# ABS_ENC_IF.net
KiCad netlist of a schematic drawn in Altium Designer
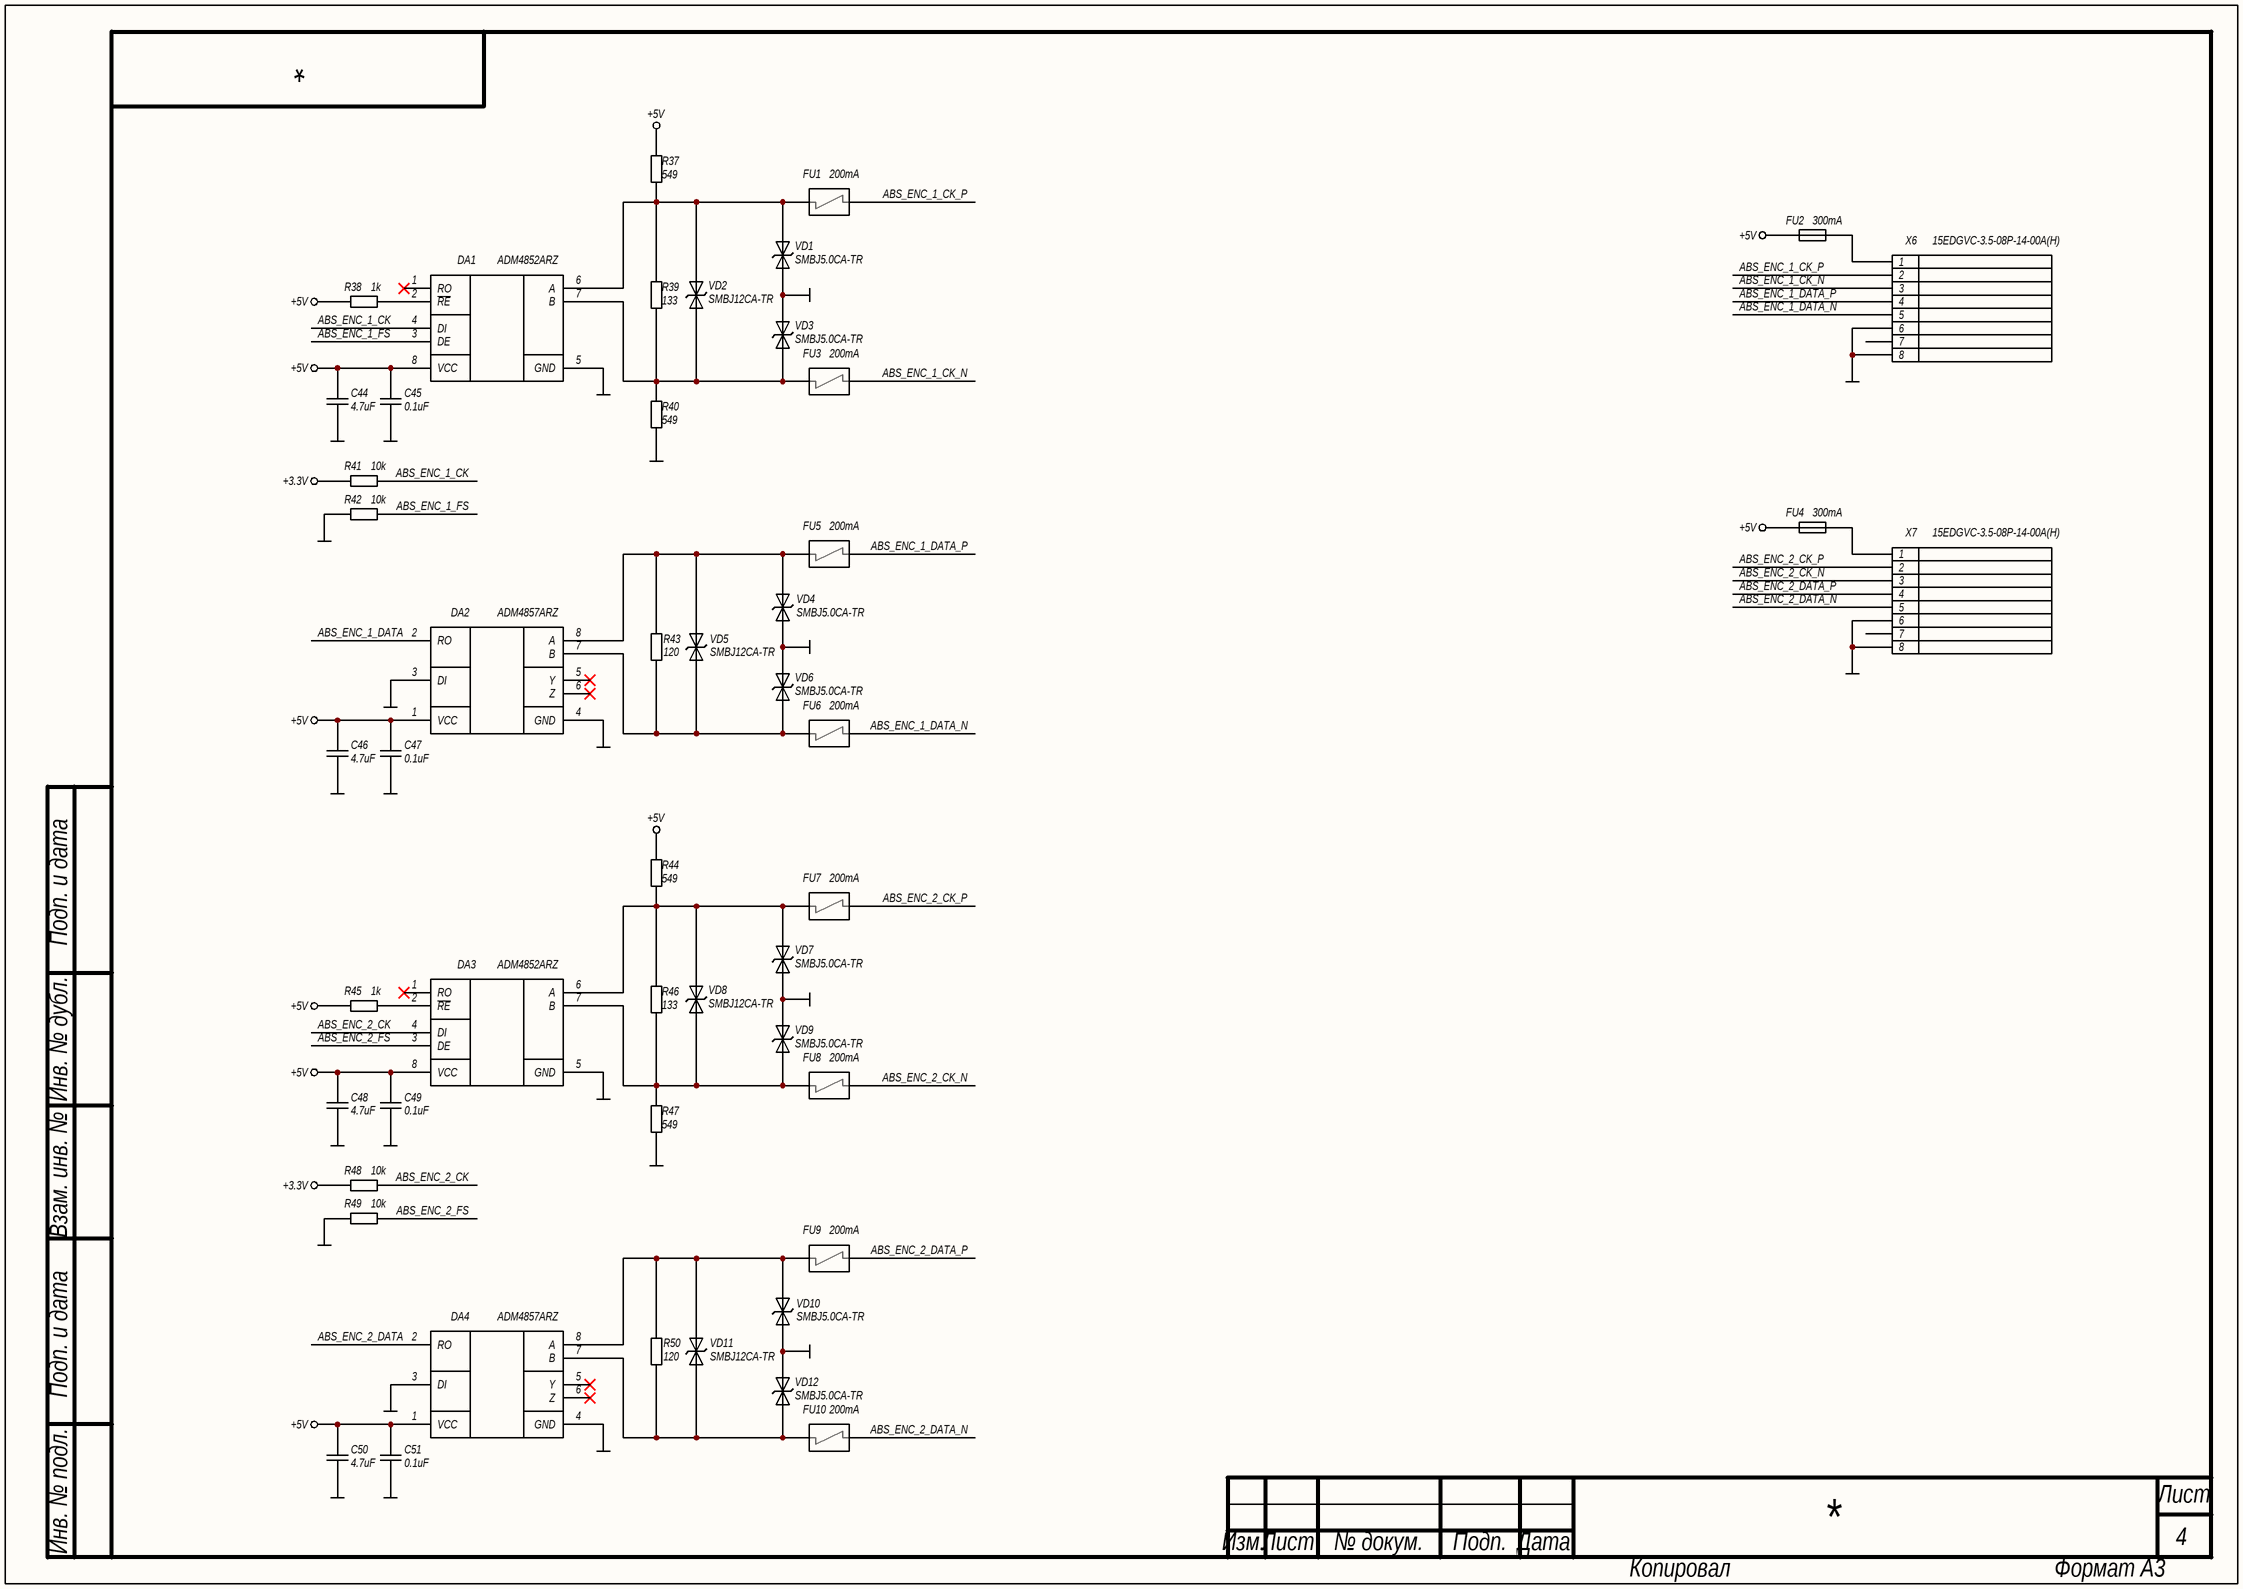
[diagram p0: ABS_ENC_IF.SchDoc]

(export (version "E")
  (design (tool "Eeschema 10.0.6"))
  (components
    (comp (ref "C44")
      (value "4.7uF")
      (footprint "C0603N")
      (description "Конденсатор")
      (libsource (lib "Components Library") (part "CAP_FIXED"))
    )
    (comp (ref "C45")
      (value "0.1uF")
      (footprint "C0603N")
      (description "Конденсатор")
      (libsource (lib "Components Library") (part "CAP_FIXED"))
    )
    (comp (ref "C46")
      (value "4.7uF")
      (footprint "C0603N")
      (description "Конденсатор")
      (libsource (lib "Components Library") (part "CAP_FIXED"))
    )
    (comp (ref "C47")
      (value "0.1uF")
      (footprint "C0603N")
      (description "Конденсатор")
      (libsource (lib "Components Library") (part "CAP_FIXED"))
    )
    (comp (ref "C48")
      (value "4.7uF")
      (footprint "C0603N")
      (description "Конденсатор")
      (libsource (lib "Components Library") (part "CAP_FIXED"))
    )
    (comp (ref "C49")
      (value "0.1uF")
      (footprint "C0603N")
      (description "Конденсатор")
      (libsource (lib "Components Library") (part "CAP_FIXED"))
    )
    (comp (ref "C50")
      (value "4.7uF")
      (footprint "C0603N")
      (description "Конденсатор")
      (libsource (lib "Components Library") (part "CAP_FIXED"))
    )
    (comp (ref "C51")
      (value "0.1uF")
      (footprint "C0603N")
      (description "Конденсатор")
      (libsource (lib "Components Library") (part "CAP_FIXED"))
    )
    (comp (ref "DA1")
      (value "ADM4852ARZ")
      (footprint "SOIC8")
      (description "Микросхема интерфейса RS485")
      (libsource (lib "Components Library") (part "ADM4852A"))
    )
    (comp (ref "DA2")
      (value "ADM4857ARZ")
      (footprint "SOIC8")
      (description "Микросхема интерфейса RS485")
      (libsource (lib "Components Library") (part "ADM4857A"))
    )
    (comp (ref "DA3")
      (value "ADM4852ARZ")
      (footprint "SOIC8")
      (description "Микросхема интерфейса RS485")
      (libsource (lib "Components Library") (part "ADM4852A"))
    )
    (comp (ref "DA4")
      (value "ADM4857ARZ")
      (footprint "SOIC8")
      (description "Микросхема интерфейса RS485")
      (libsource (lib "Components Library") (part "ADM4857A"))
    )
    (comp (ref "FU1")
      (value "200mA")
      (footprint "TBU-CA")
      (description "Полупроводниковый предохранитель")
      (libsource (lib "Components Library") (part "FUSE_TBU"))
    )
    (comp (ref "FU2")
      (value "300mA")
      (footprint "MF-MSMF")
      (description "Плавкий предохранитель")
      (libsource (lib "Components Library") (part "FUSE"))
    )
    (comp (ref "FU3")
      (value "200mA")
      (footprint "TBU-CA")
      (description "Полупроводниковый предохранитель")
      (libsource (lib "Components Library") (part "FUSE_TBU"))
    )
    (comp (ref "FU4")
      (value "300mA")
      (footprint "MF-MSMF")
      (description "Плавкий предохранитель")
      (libsource (lib "Components Library") (part "FUSE"))
    )
    (comp (ref "FU5")
      (value "200mA")
      (footprint "TBU-CA")
      (description "Полупроводниковый предохранитель")
      (libsource (lib "Components Library") (part "FUSE_TBU"))
    )
    (comp (ref "FU6")
      (value "200mA")
      (footprint "TBU-CA")
      (description "Полупроводниковый предохранитель")
      (libsource (lib "Components Library") (part "FUSE_TBU"))
    )
    (comp (ref "FU7")
      (value "200mA")
      (footprint "TBU-CA")
      (description "Полупроводниковый предохранитель")
      (libsource (lib "Components Library") (part "FUSE_TBU"))
    )
    (comp (ref "FU8")
      (value "200mA")
      (footprint "TBU-CA")
      (description "Полупроводниковый предохранитель")
      (libsource (lib "Components Library") (part "FUSE_TBU"))
    )
    (comp (ref "FU9")
      (value "200mA")
      (footprint "TBU-CA")
      (description "Полупроводниковый предохранитель")
      (libsource (lib "Components Library") (part "FUSE_TBU"))
    )
    (comp (ref "FU10")
      (value "200mA")
      (footprint "TBU-CA")
      (description "Полупроводниковый предохранитель")
      (libsource (lib "Components Library") (part "FUSE_TBU"))
    )
    (comp (ref "R37")
      (value "549")
      (footprint "R0805N")
      (description "Резистор")
      (libsource (lib "") (part "RES_FIXED_2"))
    )
    (comp (ref "R38")
      (value "1k")
      (footprint "R0603N")
      (description "Резистор")
      (libsource (lib "Components Library") (part "RES_FIXED"))
    )
    (comp (ref "R39")
      (value "133")
      (footprint "R0805N")
      (description "Резистор")
      (libsource (lib "") (part "RES_FIXED_2"))
    )
    (comp (ref "R40")
      (value "549")
      (footprint "R0805N")
      (description "Резистор")
      (libsource (lib "") (part "RES_FIXED_2"))
    )
    (comp (ref "R41")
      (value "10k")
      (footprint "R0603N")
      (description "Резистор")
      (libsource (lib "Components Library") (part "RES_FIXED"))
    )
    (comp (ref "R42")
      (value "10k")
      (footprint "R0603N")
      (description "Резистор")
      (libsource (lib "Components Library") (part "RES_FIXED"))
    )
    (comp (ref "R43")
      (value "120")
      (footprint "R0805N")
      (description "Резистор")
      (libsource (lib "") (part "RES_FIXED_1"))
    )
    (comp (ref "R44")
      (value "549")
      (footprint "R0805N")
      (description "Резистор")
      (libsource (lib "") (part "RES_FIXED_2"))
    )
    (comp (ref "R45")
      (value "1k")
      (footprint "R0603N")
      (description "Резистор")
      (libsource (lib "Components Library") (part "RES_FIXED"))
    )
    (comp (ref "R46")
      (value "133")
      (footprint "R0805N")
      (description "Резистор")
      (libsource (lib "") (part "RES_FIXED_2"))
    )
    (comp (ref "R47")
      (value "549")
      (footprint "R0805N")
      (description "Резистор")
      (libsource (lib "") (part "RES_FIXED_2"))
    )
    (comp (ref "R48")
      (value "10k")
      (footprint "R0603N")
      (description "Резистор")
      (libsource (lib "Components Library") (part "RES_FIXED"))
    )
    (comp (ref "R49")
      (value "10k")
      (footprint "R0603N")
      (description "Резистор")
      (libsource (lib "Components Library") (part "RES_FIXED"))
    )
    (comp (ref "R50")
      (value "120")
      (footprint "R0805N")
      (description "Резистор")
      (libsource (lib "") (part "RES_FIXED_1"))
    )
    (comp (ref "VD1")
      (value "SMBJ5.0CA-TR")
      (footprint "SMB")
      (description "TVS диод двунаправленный")
      (libsource (lib "Components Library") (part "TVS_BIDIR"))
    )
    (comp (ref "VD2")
      (value "SMBJ12CA-TR")
      (footprint "SMB")
      (description "TVS диод двунаправленный")
      (libsource (lib "Components Library") (part "TVS_BIDIR"))
    )
    (comp (ref "VD3")
      (value "SMBJ5.0CA-TR")
      (footprint "SMB")
      (description "TVS диод двунаправленный")
      (libsource (lib "Components Library") (part "TVS_BIDIR"))
    )
    (comp (ref "VD4")
      (value "SMBJ5.0CA-TR")
      (footprint "SMB")
      (description "TVS диод двунаправленный")
      (libsource (lib "Components Library") (part "TVS_BIDIR"))
    )
    (comp (ref "VD5")
      (value "SMBJ12CA-TR")
      (footprint "SMB")
      (description "TVS диод двунаправленный")
      (libsource (lib "Components Library") (part "TVS_BIDIR"))
    )
    (comp (ref "VD6")
      (value "SMBJ5.0CA-TR")
      (footprint "SMB")
      (description "TVS диод двунаправленный")
      (libsource (lib "Components Library") (part "TVS_BIDIR"))
    )
    (comp (ref "VD7")
      (value "SMBJ5.0CA-TR")
      (footprint "SMB")
      (description "TVS диод двунаправленный")
      (libsource (lib "Components Library") (part "TVS_BIDIR"))
    )
    (comp (ref "VD8")
      (value "SMBJ12CA-TR")
      (footprint "SMB")
      (description "TVS диод двунаправленный")
      (libsource (lib "Components Library") (part "TVS_BIDIR"))
    )
    (comp (ref "VD9")
      (value "SMBJ5.0CA-TR")
      (footprint "SMB")
      (description "TVS диод двунаправленный")
      (libsource (lib "Components Library") (part "TVS_BIDIR"))
    )
    (comp (ref "VD10")
      (value "SMBJ5.0CA-TR")
      (footprint "SMB")
      (description "TVS диод двунаправленный")
      (libsource (lib "Components Library") (part "TVS_BIDIR"))
    )
    (comp (ref "VD11")
      (value "SMBJ12CA-TR")
      (footprint "SMB")
      (description "TVS диод двунаправленный")
      (libsource (lib "Components Library") (part "TVS_BIDIR"))
    )
    (comp (ref "VD12")
      (value "SMBJ5.0CA-TR")
      (footprint "SMB")
      (description "TVS диод двунаправленный")
      (libsource (lib "Components Library") (part "TVS_BIDIR"))
    )
    (comp (ref "X6")
      (value "15EDGVC-3.5-08P-14-00A(H)")
      (footprint "15EDGVC-3.5-08P-14-00A(H)")
      (description "Разъем, 8 контактов")
      (libsource (lib "Components Library") (part "Connector 8"))
    )
    (comp (ref "X7")
      (value "15EDGVC-3.5-08P-14-00A(H)")
      (footprint "15EDGVC-3.5-08P-14-00A(H)")
      (description "Разъем, 8 контактов")
      (libsource (lib "Components Library") (part "Connector 8"))
    )
  )
  (nets
    (net (code "1") (name "+3.3V") (class "Default")
      (node (ref "R41") (pin "2") (pinfunction "2_2") (pintype "passive"))
      (node (ref "R48") (pin "2") (pinfunction "2_2") (pintype "passive"))
    )
    (net (code "2") (name "+5V") (class "Default")
      (node (ref "C44") (pin "2") (pinfunction "2_2") (pintype "passive"))
      (node (ref "C45") (pin "2") (pinfunction "2_2") (pintype "passive"))
      (node (ref "C46") (pin "2") (pinfunction "2_2") (pintype "passive"))
      (node (ref "C47") (pin "2") (pinfunction "2_2") (pintype "passive"))
      (node (ref "C48") (pin "2") (pinfunction "2_2") (pintype "passive"))
      (node (ref "C49") (pin "2") (pinfunction "2_2") (pintype "passive"))
      (node (ref "C50") (pin "2") (pinfunction "2_2") (pintype "passive"))
      (node (ref "C51") (pin "2") (pinfunction "2_2") (pintype "passive"))
      (node (ref "DA1") (pin "8") (pinfunction "VCC_8") (pintype "power_in"))
      (node (ref "DA2") (pin "1") (pinfunction "VCC_1") (pintype "power_in"))
      (node (ref "DA3") (pin "8") (pinfunction "VCC_8") (pintype "power_in"))
      (node (ref "DA4") (pin "1") (pinfunction "VCC_1") (pintype "power_in"))
      (node (ref "FU2") (pin "1") (pinfunction "1_1") (pintype "passive"))
      (node (ref "FU4") (pin "1") (pinfunction "1_1") (pintype "passive"))
      (node (ref "R37") (pin "2") (pinfunction "2_2") (pintype "passive"))
      (node (ref "R38") (pin "2") (pinfunction "2_2") (pintype "passive"))
      (node (ref "R44") (pin "2") (pinfunction "2_2") (pintype "passive"))
      (node (ref "R45") (pin "2") (pinfunction "2_2") (pintype "passive"))
    )
    (net (code "3") (name "/ABS_ENC_1_CK") (class "Default")
      (node (ref "DA1") (pin "4") (pinfunction "DI_4") (pintype "power_in"))
      (node (ref "R41") (pin "1") (pinfunction "1_1") (pintype "passive"))
    )
    (net (code "4") (name "/ABS_ENC_1_CK_N") (class "Default")
      (node (ref "FU3") (pin "3") (pinfunction "IN/OUT_3") (pintype "passive"))
      (node (ref "X6") (pin "3") (pinfunction "3_3") (pintype "power_in"))
    )
    (net (code "5") (name "/ABS_ENC_1_CK_P") (class "Default")
      (node (ref "FU1") (pin "3") (pinfunction "IN/OUT_3") (pintype "passive"))
      (node (ref "X6") (pin "2") (pinfunction "2_2") (pintype "power_in"))
    )
    (net (code "6") (name "/ABS_ENC_1_DATA") (class "Default")
      (node (ref "DA2") (pin "2") (pinfunction "RO_2") (pintype "power_in"))
    )
    (net (code "7") (name "/ABS_ENC_1_DATA_N") (class "Default")
      (node (ref "FU6") (pin "3") (pinfunction "IN/OUT_3") (pintype "passive"))
      (node (ref "X6") (pin "5") (pinfunction "5_5") (pintype "power_in"))
    )
    (net (code "8") (name "/ABS_ENC_1_DATA_P") (class "Default")
      (node (ref "FU5") (pin "3") (pinfunction "IN/OUT_3") (pintype "passive"))
      (node (ref "X6") (pin "4") (pinfunction "4_4") (pintype "power_in"))
    )
    (net (code "9") (name "/ABS_ENC_1_FS") (class "Default")
      (node (ref "DA1") (pin "3") (pinfunction "DE_3") (pintype "power_in"))
      (node (ref "R42") (pin "1") (pinfunction "1_1") (pintype "passive"))
    )
    (net (code "10") (name "/ABS_ENC_2_CK") (class "Default")
      (node (ref "DA3") (pin "4") (pinfunction "DI_4") (pintype "power_in"))
      (node (ref "R48") (pin "1") (pinfunction "1_1") (pintype "passive"))
    )
    (net (code "11") (name "/ABS_ENC_2_CK_N") (class "Default")
      (node (ref "FU8") (pin "3") (pinfunction "IN/OUT_3") (pintype "passive"))
      (node (ref "X7") (pin "3") (pinfunction "3_3") (pintype "power_in"))
    )
    (net (code "12") (name "/ABS_ENC_2_CK_P") (class "Default")
      (node (ref "FU7") (pin "3") (pinfunction "IN/OUT_3") (pintype "passive"))
      (node (ref "X7") (pin "2") (pinfunction "2_2") (pintype "power_in"))
    )
    (net (code "13") (name "/ABS_ENC_2_DATA") (class "Default")
      (node (ref "DA4") (pin "2") (pinfunction "RO_2") (pintype "power_in"))
    )
    (net (code "14") (name "/ABS_ENC_2_DATA_N") (class "Default")
      (node (ref "FU10") (pin "3") (pinfunction "IN/OUT_3") (pintype "passive"))
      (node (ref "X7") (pin "5") (pinfunction "5_5") (pintype "power_in"))
    )
    (net (code "15") (name "/ABS_ENC_2_DATA_P") (class "Default")
      (node (ref "FU9") (pin "3") (pinfunction "IN/OUT_3") (pintype "passive"))
      (node (ref "X7") (pin "4") (pinfunction "4_4") (pintype "power_in"))
    )
    (net (code "16") (name "/ABS_ENC_2_FS") (class "Default")
      (node (ref "DA3") (pin "3") (pinfunction "DE_3") (pintype "power_in"))
      (node (ref "R49") (pin "1") (pinfunction "1_1") (pintype "passive"))
    )
    (net (code "17") (name "GND") (class "Default")
      (node (ref "C44") (pin "1") (pinfunction "1_1") (pintype "passive"))
      (node (ref "C45") (pin "1") (pinfunction "1_1") (pintype "passive"))
      (node (ref "C46") (pin "1") (pinfunction "1_1") (pintype "passive"))
      (node (ref "C47") (pin "1") (pinfunction "1_1") (pintype "passive"))
      (node (ref "C48") (pin "1") (pinfunction "1_1") (pintype "passive"))
      (node (ref "C49") (pin "1") (pinfunction "1_1") (pintype "passive"))
      (node (ref "C50") (pin "1") (pinfunction "1_1") (pintype "passive"))
      (node (ref "C51") (pin "1") (pinfunction "1_1") (pintype "passive"))
      (node (ref "DA1") (pin "5") (pinfunction "GND_5") (pintype "power_in"))
      (node (ref "DA2") (pin "3") (pinfunction "DI_3") (pintype "power_in"))
      (node (ref "DA2") (pin "4") (pinfunction "GND_4") (pintype "power_in"))
      (node (ref "DA3") (pin "5") (pinfunction "GND_5") (pintype "power_in"))
      (node (ref "DA4") (pin "3") (pinfunction "DI_3") (pintype "power_in"))
      (node (ref "DA4") (pin "4") (pinfunction "GND_4") (pintype "power_in"))
      (node (ref "R40") (pin "1") (pinfunction "1_1") (pintype "passive"))
      (node (ref "R42") (pin "2") (pinfunction "2_2") (pintype "passive"))
      (node (ref "R47") (pin "1") (pinfunction "1_1") (pintype "passive"))
      (node (ref "R49") (pin "2") (pinfunction "2_2") (pintype "passive"))
      (node (ref "VD1") (pin "2") (pinfunction "A2_2") (pintype "passive"))
      (node (ref "VD10") (pin "2") (pinfunction "A2_2") (pintype "passive"))
      (node (ref "VD12") (pin "2") (pinfunction "A2_2") (pintype "passive"))
      (node (ref "VD3") (pin "2") (pinfunction "A2_2") (pintype "passive"))
      (node (ref "VD4") (pin "2") (pinfunction "A2_2") (pintype "passive"))
      (node (ref "VD6") (pin "2") (pinfunction "A2_2") (pintype "passive"))
      (node (ref "VD7") (pin "2") (pinfunction "A2_2") (pintype "passive"))
      (node (ref "VD9") (pin "2") (pinfunction "A2_2") (pintype "passive"))
      (node (ref "X6") (pin "6") (pinfunction "6_6") (pintype "power_in"))
      (node (ref "X6") (pin "8") (pinfunction "8_8") (pintype "power_in"))
      (node (ref "X7") (pin "6") (pinfunction "6_6") (pintype "power_in"))
      (node (ref "X7") (pin "8") (pinfunction "8_8") (pintype "power_in"))
    )
    (net (code "18") (name "Net-(DA1-A)") (class "Default")
      (node (ref "DA1") (pin "6") (pinfunction "A_6") (pintype "power_in"))
      (node (ref "FU1") (pin "1") (pinfunction "IN/OUT_1") (pintype "passive"))
      (node (ref "R37") (pin "1") (pinfunction "1_1") (pintype "passive"))
      (node (ref "R39") (pin "2") (pinfunction "2_2") (pintype "passive"))
      (node (ref "VD1") (pin "1") (pinfunction "A1_1") (pintype "passive"))
      (node (ref "VD2") (pin "1") (pinfunction "A1_1") (pintype "passive"))
    )
    (net (code "19") (name "Net-(DA1-B)") (class "Default")
      (node (ref "DA1") (pin "7") (pinfunction "B_7") (pintype "power_in"))
      (node (ref "FU3") (pin "1") (pinfunction "IN/OUT_1") (pintype "passive"))
      (node (ref "R39") (pin "1") (pinfunction "1_1") (pintype "passive"))
      (node (ref "R40") (pin "2") (pinfunction "2_2") (pintype "passive"))
      (node (ref "VD2") (pin "2") (pinfunction "A2_2") (pintype "passive"))
      (node (ref "VD3") (pin "1") (pinfunction "A1_1") (pintype "passive"))
    )
    (net (code "20") (name "Net-(DA1-~{RE})") (class "Default")
      (node (ref "DA1") (pin "2") (pinfunction "~{RE}_2") (pintype "power_in"))
      (node (ref "R38") (pin "1") (pinfunction "1_1") (pintype "passive"))
    )
    (net (code "21") (name "Net-(DA2-A)") (class "Default")
      (node (ref "DA2") (pin "8") (pinfunction "A_8") (pintype "power_in"))
      (node (ref "FU5") (pin "1") (pinfunction "IN/OUT_1") (pintype "passive"))
      (node (ref "R43") (pin "1") (pinfunction "1_1") (pintype "passive"))
      (node (ref "VD4") (pin "1") (pinfunction "A1_1") (pintype "passive"))
      (node (ref "VD5") (pin "1") (pinfunction "A1_1") (pintype "passive"))
    )
    (net (code "22") (name "Net-(DA2-B)") (class "Default")
      (node (ref "DA2") (pin "7") (pinfunction "B_7") (pintype "power_in"))
      (node (ref "FU6") (pin "1") (pinfunction "IN/OUT_1") (pintype "passive"))
      (node (ref "R43") (pin "2") (pinfunction "2_2") (pintype "passive"))
      (node (ref "VD5") (pin "2") (pinfunction "A2_2") (pintype "passive"))
      (node (ref "VD6") (pin "1") (pinfunction "A1_1") (pintype "passive"))
    )
    (net (code "23") (name "Net-(DA3-A)") (class "Default")
      (node (ref "DA3") (pin "6") (pinfunction "A_6") (pintype "power_in"))
      (node (ref "FU7") (pin "1") (pinfunction "IN/OUT_1") (pintype "passive"))
      (node (ref "R44") (pin "1") (pinfunction "1_1") (pintype "passive"))
      (node (ref "R46") (pin "2") (pinfunction "2_2") (pintype "passive"))
      (node (ref "VD7") (pin "1") (pinfunction "A1_1") (pintype "passive"))
      (node (ref "VD8") (pin "1") (pinfunction "A1_1") (pintype "passive"))
    )
    (net (code "24") (name "Net-(DA3-B)") (class "Default")
      (node (ref "DA3") (pin "7") (pinfunction "B_7") (pintype "power_in"))
      (node (ref "FU8") (pin "1") (pinfunction "IN/OUT_1") (pintype "passive"))
      (node (ref "R46") (pin "1") (pinfunction "1_1") (pintype "passive"))
      (node (ref "R47") (pin "2") (pinfunction "2_2") (pintype "passive"))
      (node (ref "VD8") (pin "2") (pinfunction "A2_2") (pintype "passive"))
      (node (ref "VD9") (pin "1") (pinfunction "A1_1") (pintype "passive"))
    )
    (net (code "25") (name "Net-(DA3-~{RE})") (class "Default")
      (node (ref "DA3") (pin "2") (pinfunction "~{RE}_2") (pintype "power_in"))
      (node (ref "R45") (pin "1") (pinfunction "1_1") (pintype "passive"))
    )
    (net (code "26") (name "Net-(DA4-A)") (class "Default")
      (node (ref "DA4") (pin "8") (pinfunction "A_8") (pintype "power_in"))
      (node (ref "FU9") (pin "1") (pinfunction "IN/OUT_1") (pintype "passive"))
      (node (ref "R50") (pin "1") (pinfunction "1_1") (pintype "passive"))
      (node (ref "VD10") (pin "1") (pinfunction "A1_1") (pintype "passive"))
      (node (ref "VD11") (pin "1") (pinfunction "A1_1") (pintype "passive"))
    )
    (net (code "27") (name "Net-(DA4-B)") (class "Default")
      (node (ref "DA4") (pin "7") (pinfunction "B_7") (pintype "power_in"))
      (node (ref "FU10") (pin "1") (pinfunction "IN/OUT_1") (pintype "passive"))
      (node (ref "R50") (pin "2") (pinfunction "2_2") (pintype "passive"))
      (node (ref "VD11") (pin "2") (pinfunction "A2_2") (pintype "passive"))
      (node (ref "VD12") (pin "1") (pinfunction "A1_1") (pintype "passive"))
    )
    (net (code "28") (name "Net-(FU2-Pad2)") (class "Default")
      (node (ref "FU2") (pin "2") (pinfunction "2_2") (pintype "passive"))
      (node (ref "X6") (pin "1") (pinfunction "1_1") (pintype "power_in"))
    )
    (net (code "29") (name "Net-(FU4-Pad2)") (class "Default")
      (node (ref "FU4") (pin "2") (pinfunction "2_2") (pintype "passive"))
      (node (ref "X7") (pin "1") (pinfunction "1_1") (pintype "power_in"))
    )
    (net (code "30") (name "unconnected-(DA1-RO-Pad1)") (class "Default")
      (node (ref "DA1") (pin "1") (pinfunction "RO_1") (pintype "power_in+no_connect"))
    )
    (net (code "31") (name "unconnected-(DA2-Y-Pad5)") (class "Default")
      (node (ref "DA2") (pin "5") (pinfunction "Y_5") (pintype "power_in+no_connect"))
    )
    (net (code "32") (name "unconnected-(DA2-Z-Pad6)") (class "Default")
      (node (ref "DA2") (pin "6") (pinfunction "Z_6") (pintype "power_in+no_connect"))
    )
    (net (code "33") (name "unconnected-(DA3-RO-Pad1)") (class "Default")
      (node (ref "DA3") (pin "1") (pinfunction "RO_1") (pintype "power_in+no_connect"))
    )
    (net (code "34") (name "unconnected-(DA4-Y-Pad5)") (class "Default")
      (node (ref "DA4") (pin "5") (pinfunction "Y_5") (pintype "power_in+no_connect"))
    )
    (net (code "35") (name "unconnected-(DA4-Z-Pad6)") (class "Default")
      (node (ref "DA4") (pin "6") (pinfunction "Z_6") (pintype "power_in+no_connect"))
    )
    (net (code "36") (name "unconnected-(X6-Pad7)") (class "Default")
      (node (ref "X6") (pin "7") (pinfunction "7_7") (pintype "power_in"))
    )
    (net (code "37") (name "unconnected-(X7-Pad7)") (class "Default")
      (node (ref "X7") (pin "7") (pinfunction "7_7") (pintype "power_in"))
    )
  )
)
